# BatteryControl.net
KiCad netlist of a schematic drawn in Altium Designer
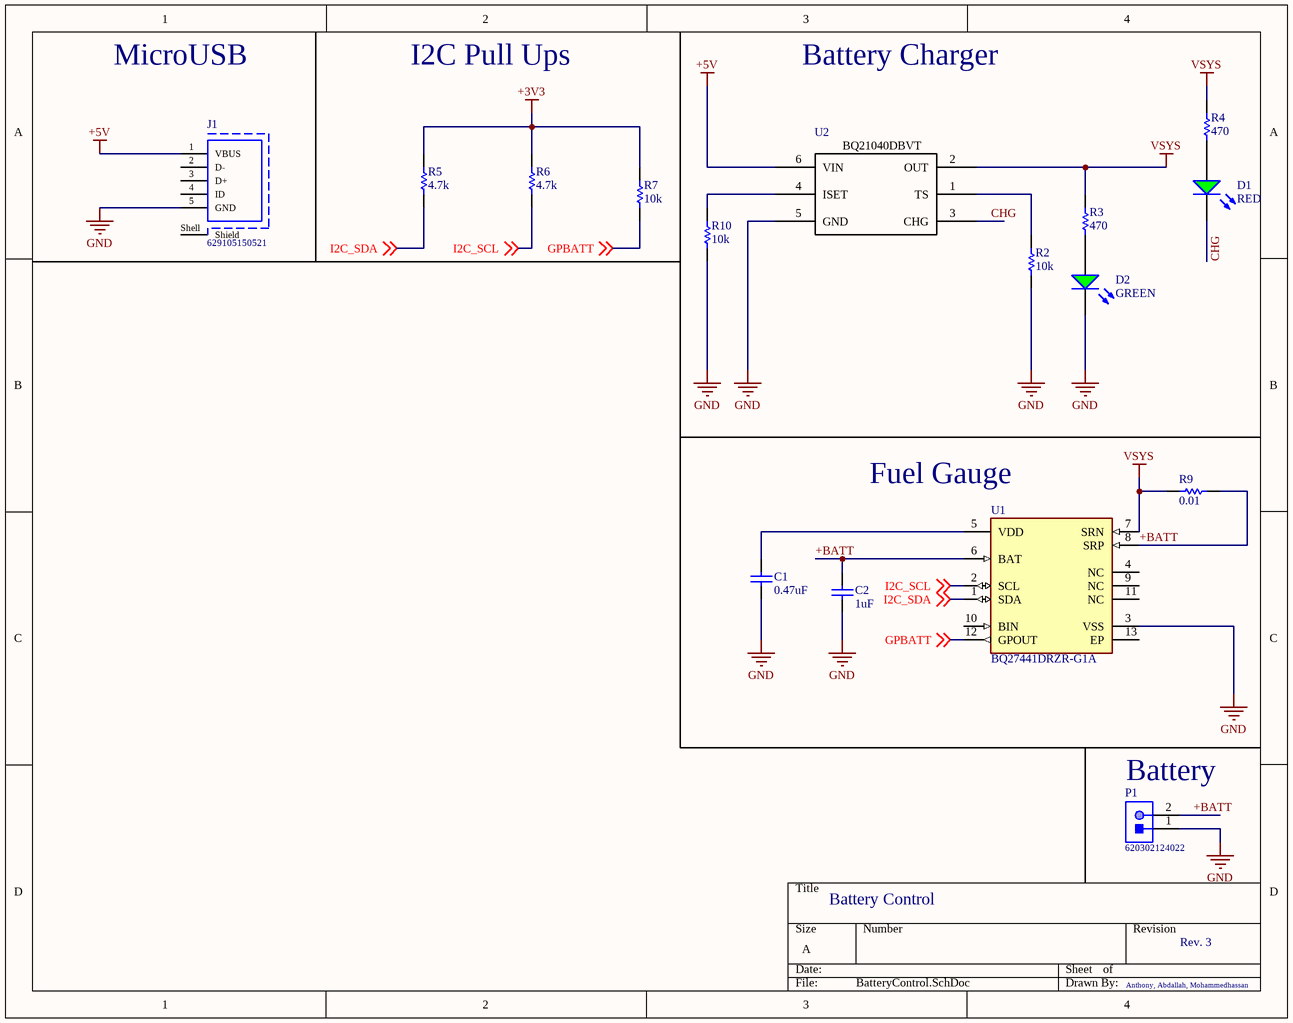
[diagram p0: BatteryControl.SchDoc]

(export (version "E")
  (design (tool "Eeschema 10.0.6"))
  (components
    (comp (ref "C1")
      (value "0.47uF")
      (footprint "CAPC2013X145X50LL20T25")
      (fields (field (name "MANUFACTURER") "Kemet") (field (name "PART NUMBER") "C0805C105K4PACTU"))
      (libsource (lib "Altium Content Vault") (part "CAP"))
    )
    (comp (ref "C2")
      (value "1uF")
      (footprint "CAPC2013X145X50LL20T25")
      (fields (field (name "MANUFACTURER") "Kemet") (field (name "PART NUMBER") "C0805C105K4PACTU"))
      (libsource (lib "Altium Content Vault") (part "CAP"))
    )
    (comp (ref "D1")
      (value "RED")
      (footprint "LUMX-SML-LX0603_V")
      (description "LED Green Diode, 18 mcd, 50 mW, -25 to 85 degC, 2-Pin SMD, RoHS, Tape and Reel")
      (fields (field (name "MANUFACTURER") "Lumex") (field (name "PART NO") "SML-LX0603GW-TR"))
      (libsource (lib "Altium Content Vault") (part "LED-GREEN-AK-2"))
    )
    (comp (ref "D2")
      (value "GREEN")
      (footprint "LUMX-SML-LX0603_V")
      (description "LED Green Diode, 18 mcd, 50 mW, -25 to 85 degC, 2-Pin SMD, RoHS, Tape and Reel")
      (fields (field (name "MANUFACTURER") "Lumex") (field (name "PART NO") "SML-LX0603GW-TR"))
      (libsource (lib "Altium Content Vault") (part "LED-GREEN-AK-2"))
    )
    (comp (ref "J1")
      (value "629105150521")
      (footprint "629105150521")
      (description "Micro USB 2.0 Type B Receptacle WR-COM, Horizontal, SMT, with Pegs, High Current at Pin 1 & Pin 5")
      (fields (field (name "MANUFACTURER") "Wurth Elektronik") (field (name "PUBLISHER") "WurthElektronik"))
      (libsource (lib "Altium Content Vault") (part "WE-USB-5-1SHLD"))
    )
    (comp (ref "P1")
      (value "620302124022")
      (footprint "620302124022")
      (description "Male Shrouded Header WR-WTB, SMT, Vertical, pitch 2 mm, 1 x 2 position")
      (fields (field (name "MANUFACTURER") "Wurth Elektronik") (field (name "PUBLISHER") "WurthElektronik"))
      (libsource (lib "Altium Content Vault") (part "WE-CN-1P-M-R2"))
    )
    (comp (ref "R2")
      (value "10k")
      (footprint "RESC2013X60X40ML20T25")
      (fields (field (name "PART NUMBER") "ERA6AEB472V") (field (name "MANUFACTURER") "Panasonic"))
      (libsource (lib "Altium Content Vault") (part "RES"))
    )
    (comp (ref "R3")
      (value "470")
      (footprint "RESC2013X60X40ML20T25")
      (fields (field (name "PART NUMBER") "ERA6AEB472V") (field (name "MANUFACTURER") "Panasonic"))
      (libsource (lib "Altium Content Vault") (part "RES"))
    )
    (comp (ref "R4")
      (value "470")
      (footprint "RESC2013X60X40ML20T25")
      (fields (field (name "PART NUMBER") "ERA6AEB472V") (field (name "MANUFACTURER") "Panasonic"))
      (libsource (lib "Altium Content Vault") (part "RES"))
    )
    (comp (ref "R5")
      (value "4.7k")
      (footprint "RESC2013X60X40ML20T25")
      (fields (field (name "PART NUMBER") "ERA6AEB472V") (field (name "MANUFACTURER") "Panasonic"))
      (libsource (lib "Altium Content Vault") (part "RES"))
    )
    (comp (ref "R6")
      (value "4.7k")
      (footprint "RESC2013X60X40ML20T25")
      (fields (field (name "PART NUMBER") "ERA6AEB472V") (field (name "MANUFACTURER") "Panasonic"))
      (libsource (lib "Altium Content Vault") (part "RES"))
    )
    (comp (ref "R7")
      (value "10k")
      (footprint "RESC2013X60X40ML20T25")
      (fields (field (name "PART NUMBER") "ERA6AEB472V") (field (name "MANUFACTURER") "Panasonic"))
      (libsource (lib "Altium Content Vault") (part "RES"))
    )
    (comp (ref "R9")
      (value "0.01")
      (footprint "RESC2013X60X40ML20T25")
      (fields (field (name "PART NUMBER") "ERA6AEB472V") (field (name "MANUFACTURER") "Panasonic"))
      (libsource (lib "Altium Content Vault") (part "RES"))
    )
    (comp (ref "R10")
      (value "10k")
      (footprint "RESC2013X60X40ML20T25")
      (fields (field (name "PART NUMBER") "ERA6AEB472V") (field (name "MANUFACTURER") "Panasonic"))
      (libsource (lib "Altium Content Vault") (part "RES"))
    )
    (comp (ref "U1")
      (value "BQ27441DRZR-G1A")
      (footprint "FP-DRZ0012A-MFG")
      (description "IC BATT FUEL GAUGE LI-ION 12SON")
      (fields
        (field (name "OCTOPART") "https://octopart.com/bq27441drzr-g1a-texas+instruments-30555829")
        (field (name "MANUFACTURER") "Texas Instruments")
      )
      (libsource (lib "Altium Content Vault") (part "0f562f18464a1f07b55dcd927f1fdf2"))
    )
    (comp (ref "U2")
      (value "Component_1")
      (footprint "BQ21040DBVT")
      (libsource (lib "BatteryControl") (part "Component_1"))
    )
  )
  (nets
    (net (code "1") (name "+3V3") (class "Default")
      (node (ref "R5") (pin "2") (pinfunction "2_2") (pintype "passive"))
      (node (ref "R6") (pin "2") (pinfunction "2_2") (pintype "passive"))
      (node (ref "R7") (pin "2") (pinfunction "2_2") (pintype "passive"))
    )
    (net (code "2") (name "+5V") (class "Default")
      (node (ref "J1") (pin "1") (pinfunction "VBUS_1") (pintype "passive"))
      (node (ref "U2") (pin "6") (pinfunction "VIN_6") (pintype "passive"))
    )
    (net (code "3") (name "/+BATT") (class "Default")
      (node (ref "C2") (pin "2") (pinfunction "2_2") (pintype "passive"))
      (node (ref "P1") (pin "2") (pinfunction "2_2") (pintype "passive"))
      (node (ref "R9") (pin "1") (pinfunction "1_1") (pintype "passive"))
      (node (ref "U1") (pin "6") (pinfunction "BAT_6") (pintype "input"))
      (node (ref "U1") (pin "8") (pinfunction "SRP_8") (pintype "input"))
    )
    (net (code "4") (name "/CHG") (class "Default")
      (node (ref "D1") (pin "2") (pinfunction "K_2") (pintype "passive"))
      (node (ref "U2") (pin "3") (pinfunction "CHG_3") (pintype "passive"))
    )
    (net (code "5") (name "GND") (class "Default")
      (node (ref "C1") (pin "1") (pinfunction "1_1") (pintype "passive"))
      (node (ref "C2") (pin "1") (pinfunction "1_1") (pintype "passive"))
      (node (ref "D2") (pin "2") (pinfunction "K_2") (pintype "passive"))
      (node (ref "J1") (pin "5") (pinfunction "GND_5") (pintype "passive"))
      (node (ref "P1") (pin "1") (pinfunction "1_1") (pintype "passive"))
      (node (ref "R10") (pin "1") (pinfunction "1_1") (pintype "passive"))
      (node (ref "R2") (pin "1") (pinfunction "1_1") (pintype "passive"))
      (node (ref "U1") (pin "3") (pinfunction "VSS_3") (pintype "power_in"))
      (node (ref "U2") (pin "5") (pinfunction "GND_5") (pintype "passive"))
    )
    (net (code "6") (name "GPBATT") (class "Default")
      (node (ref "R7") (pin "1") (pinfunction "1_1") (pintype "passive"))
      (node (ref "U1") (pin "12") (pinfunction "GPOUT_12") (pintype "output"))
    )
    (net (code "7") (name "I2C_SCL") (class "Default")
      (node (ref "R6") (pin "1") (pinfunction "1_1") (pintype "passive"))
      (node (ref "U1") (pin "2") (pinfunction "SCL_2") (pintype "bidirectional"))
    )
    (net (code "8") (name "I2C_SDA") (class "Default")
      (node (ref "R5") (pin "1") (pinfunction "1_1") (pintype "passive"))
      (node (ref "U1") (pin "1") (pinfunction "SDA_1") (pintype "bidirectional"))
    )
    (net (code "9") (name "Net-(D1-A)") (class "Default")
      (node (ref "D1") (pin "1") (pinfunction "A_1") (pintype "passive"))
      (node (ref "R4") (pin "1") (pinfunction "1_1") (pintype "passive"))
    )
    (net (code "10") (name "Net-(D2-A)") (class "Default")
      (node (ref "D2") (pin "1") (pinfunction "A_1") (pintype "passive"))
      (node (ref "R3") (pin "1") (pinfunction "1_1") (pintype "passive"))
    )
    (net (code "11") (name "Net-(U1-VDD)") (class "Default")
      (node (ref "C1") (pin "2") (pinfunction "2_2") (pintype "passive"))
      (node (ref "U1") (pin "5") (pinfunction "VDD_5") (pintype "power_in"))
    )
    (net (code "12") (name "Net-(U2-ISET)") (class "Default")
      (node (ref "R10") (pin "2") (pinfunction "2_2") (pintype "passive"))
      (node (ref "U2") (pin "4") (pinfunction "ISET_4") (pintype "passive"))
    )
    (net (code "13") (name "Net-(U2-TS)") (class "Default")
      (node (ref "R2") (pin "2") (pinfunction "2_2") (pintype "passive"))
      (node (ref "U2") (pin "1") (pinfunction "TS_1") (pintype "passive"))
    )
    (net (code "14") (name "VSYS") (class "Default")
      (node (ref "R3") (pin "2") (pinfunction "2_2") (pintype "passive"))
      (node (ref "R4") (pin "2") (pinfunction "2_2") (pintype "passive"))
      (node (ref "R9") (pin "2") (pinfunction "2_2") (pintype "passive"))
      (node (ref "U1") (pin "7") (pinfunction "SRN_7") (pintype "input"))
      (node (ref "U2") (pin "2") (pinfunction "OUT_2") (pintype "passive"))
    )
    (net (code "15") (name "unconnected-(J1-D+-Pad3)") (class "Default")
      (node (ref "J1") (pin "3") (pinfunction "D+_3") (pintype "passive"))
    )
    (net (code "16") (name "unconnected-(J1-D--Pad2)") (class "Default")
      (node (ref "J1") (pin "2") (pinfunction "D-_2") (pintype "passive"))
    )
    (net (code "17") (name "unconnected-(J1-ID-Pad4)") (class "Default")
      (node (ref "J1") (pin "4") (pinfunction "ID_4") (pintype "passive"))
    )
    (net (code "18") (name "unconnected-(J1-Shield-PadShell)") (class "Default")
      (node (ref "J1") (pin "Shell") (pinfunction "Shield_Shell") (pintype "passive"))
    )
    (net (code "19") (name "unconnected-(U1-BIN-Pad10)") (class "Default")
      (node (ref "U1") (pin "10") (pinfunction "BIN_10") (pintype "input"))
    )
    (net (code "20") (name "unconnected-(U1-EP-Pad13)") (class "Default")
      (node (ref "U1") (pin "13") (pinfunction "EP_13") (pintype "power_in"))
    )
    (net (code "21") (name "unconnected-(U1-NC-Pad4)") (class "Default")
      (node (ref "U1") (pin "4") (pinfunction "NC_4") (pintype "passive"))
    )
    (net (code "22") (name "unconnected-(U1-NC-Pad9)") (class "Default")
      (node (ref "U1") (pin "9") (pinfunction "NC_9") (pintype "passive"))
    )
    (net (code "23") (name "unconnected-(U1-NC-Pad11)") (class "Default")
      (node (ref "U1") (pin "11") (pinfunction "NC_11") (pintype "passive"))
    )
  )
)
